# untitled.net
KiCad netlist of a schematic drawn in EAGLE
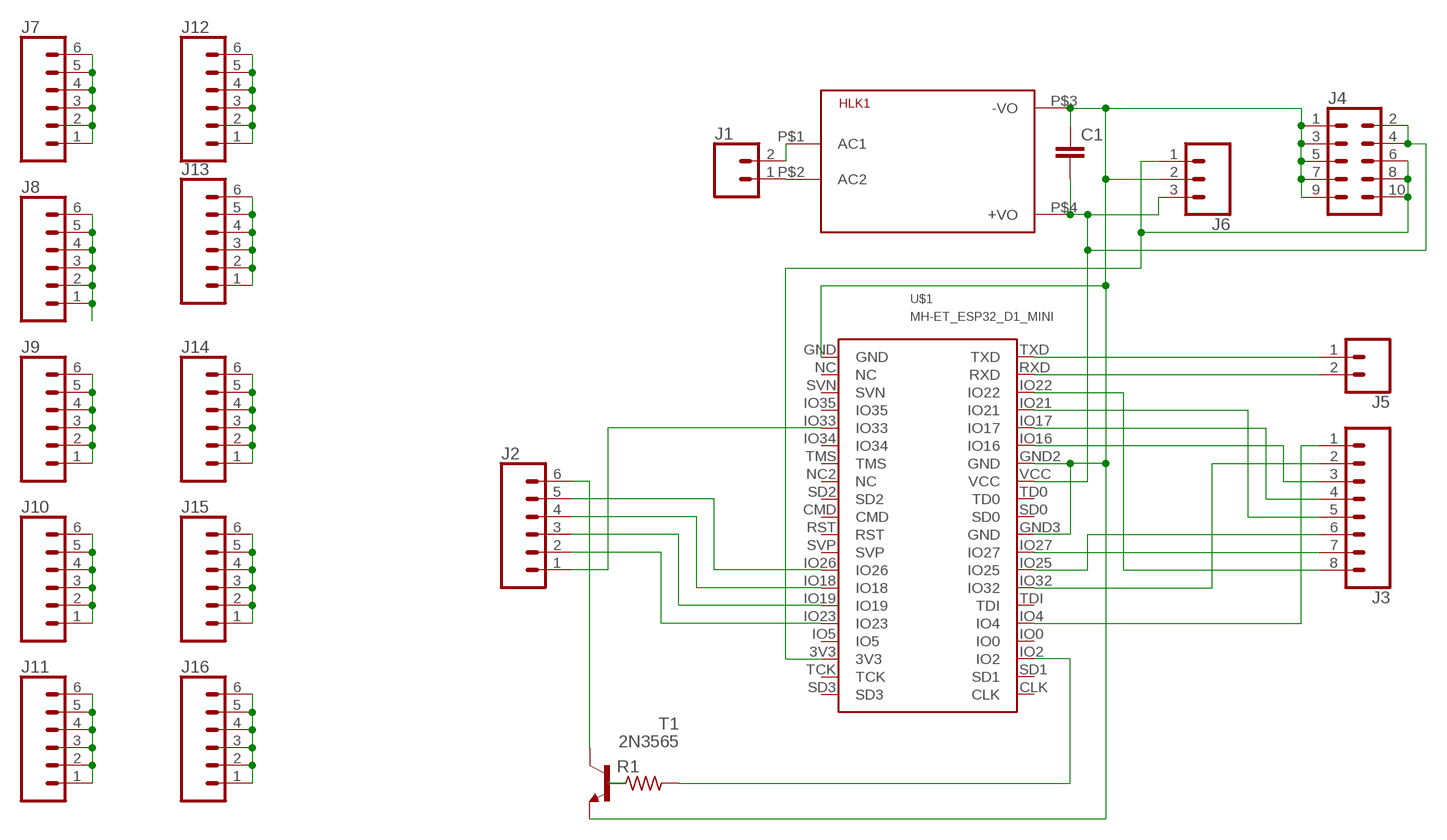
[diagram p0: schematic, sheet 1]

(export (version "E")
  (design (tool "Eeschema 10.0.6"))
  (components
    (comp (ref "C1")
      (value "C2.5/2")
      (footprint "eagle-import:C2.5-2")
      (libsource (lib "eagle-import") (part "C2.5/2"))
    )
    (comp (ref "HLK1")
      (value "HLK-PM013W")
      (footprint "eagle-import:HLK-PM01")
      (libsource (lib "eagle-import") (part "HLK-PM013W"))
    )
    (comp (ref "J1")
      (value "CONN_023.5MM")
      (footprint "eagle-import:SCREWTERMINAL-3.5MM-2")
      (libsource (lib "eagle-import") (part "CONN_023.5MM"))
    )
    (comp (ref "J2")
      (value "CONN_063.5MM-6")
      (footprint "eagle-import:SCREWTERMINAL-3.5MM-6")
      (libsource (lib "eagle-import") (part "CONN_063.5MM-6"))
    )
    (comp (ref "J3")
      (value "CONN_083.5MM-8")
      (footprint "eagle-import:SCREWTERMINAL-3.5MM-8")
      (libsource (lib "eagle-import") (part "CONN_083.5MM-8"))
    )
    (comp (ref "J4")
      (value "CONN_05X2NO_SILK")
      (footprint "eagle-import:2X5_NOSILK")
      (libsource (lib "eagle-import") (part "CONN_05X2NO_SILK"))
    )
    (comp (ref "J5")
      (value "CONN_02")
      (footprint "eagle-import:1X02")
      (libsource (lib "eagle-import") (part "CONN_02"))
    )
    (comp (ref "J6")
      (value "CONN_03SCREW")
      (footprint "eagle-import:SCREWTERMINAL-3.5MM-3")
      (libsource (lib "eagle-import") (part "CONN_03SCREW"))
    )
    (comp (ref "J7")
      (value "CONN_06SILK_FEMALE_PTH")
      (footprint "eagle-import:1X06")
      (libsource (lib "eagle-import") (part "CONN_06SILK_FEMALE_PTH"))
    )
    (comp (ref "J8")
      (value "CONN_06SILK_FEMALE_PTH")
      (footprint "eagle-import:1X06")
      (libsource (lib "eagle-import") (part "CONN_06SILK_FEMALE_PTH"))
    )
    (comp (ref "J9")
      (value "CONN_06SILK_FEMALE_PTH")
      (footprint "eagle-import:1X06")
      (libsource (lib "eagle-import") (part "CONN_06SILK_FEMALE_PTH"))
    )
    (comp (ref "J10")
      (value "CONN_06SILK_FEMALE_PTH")
      (footprint "eagle-import:1X06")
      (libsource (lib "eagle-import") (part "CONN_06SILK_FEMALE_PTH"))
    )
    (comp (ref "J11")
      (value "CONN_06SILK_FEMALE_PTH")
      (footprint "eagle-import:1X06")
      (libsource (lib "eagle-import") (part "CONN_06SILK_FEMALE_PTH"))
    )
    (comp (ref "J12")
      (value "CONN_06SILK_FEMALE_PTH")
      (footprint "eagle-import:1X06")
      (libsource (lib "eagle-import") (part "CONN_06SILK_FEMALE_PTH"))
    )
    (comp (ref "J13")
      (value "CONN_06SILK_FEMALE_PTH")
      (footprint "eagle-import:1X06")
      (libsource (lib "eagle-import") (part "CONN_06SILK_FEMALE_PTH"))
    )
    (comp (ref "J14")
      (value "CONN_06SILK_FEMALE_PTH")
      (footprint "eagle-import:1X06")
      (libsource (lib "eagle-import") (part "CONN_06SILK_FEMALE_PTH"))
    )
    (comp (ref "J15")
      (value "CONN_06SILK_FEMALE_PTH")
      (footprint "eagle-import:1X06")
      (libsource (lib "eagle-import") (part "CONN_06SILK_FEMALE_PTH"))
    )
    (comp (ref "J16")
      (value "CONN_06SILK_FEMALE_PTH")
      (footprint "eagle-import:1X06")
      (libsource (lib "eagle-import") (part "CONN_06SILK_FEMALE_PTH"))
    )
    (comp (ref "R1")
      (value "R-US_0204/5")
      (footprint "eagle-import:0204_5")
      (libsource (lib "eagle-import") (part "R-US_0204/5"))
    )
    (comp (ref "T1")
      (value "2N3565")
      (footprint "eagle-import:TO92")
      (libsource (lib "eagle-import") (part "2N3565"))
    )
    (comp (ref "U$1")
      (value "MH-ET_ESP32_D1_MINI")
      (footprint "eagle-import:MH-ET_ESP32_D1_MINI")
      (libsource (lib "eagle-import") (part "MH-ET_ESP32_D1_MINI"))
    )
  )
  (nets
    (net (code "1") (name "Net-(HLK1-+VO)") (class "Default")
      (node (ref "C1") (pin "2") (pinfunction "2_2") (pintype "passive"))
      (node (ref "HLK1") (pin "P$4") (pinfunction "+VO_P$4") (pintype "bidirectional"))
      (node (ref "J4") (pin "2") (pinfunction "2_2") (pintype "passive"))
      (node (ref "J4") (pin "4") (pinfunction "4_4") (pintype "passive"))
      (node (ref "J6") (pin "3") (pinfunction "3_3") (pintype "passive"))
      (node (ref "U$1") (pin "VCC") (pinfunction "VCC_VCC") (pintype "bidirectional"))
    )
    (net (code "2") (name "Net-(HLK1--VO)") (class "Default")
      (node (ref "C1") (pin "1") (pinfunction "1_1") (pintype "passive"))
      (node (ref "HLK1") (pin "P$3") (pinfunction "-VO_P$3") (pintype "bidirectional"))
      (node (ref "J4") (pin "1") (pinfunction "1_1") (pintype "passive"))
      (node (ref "J4") (pin "3") (pinfunction "3_3") (pintype "passive"))
      (node (ref "J4") (pin "5") (pinfunction "5_5") (pintype "passive"))
      (node (ref "J4") (pin "7") (pinfunction "7_7") (pintype "passive"))
      (node (ref "J4") (pin "9") (pinfunction "9_9") (pintype "passive"))
      (node (ref "J6") (pin "2") (pinfunction "2_2") (pintype "passive"))
      (node (ref "T1") (pin "3") (pinfunction "E_3") (pintype "passive"))
      (node (ref "U$1") (pin "GND") (pinfunction "GND_GND") (pintype "bidirectional"))
      (node (ref "U$1") (pin "GND2") (pinfunction "GND_GND2") (pintype "bidirectional"))
      (node (ref "U$1") (pin "GND3") (pinfunction "GND_GND3") (pintype "bidirectional"))
    )
    (net (code "3") (name "Net-(HLK1-AC1)") (class "Default")
      (node (ref "HLK1") (pin "P$1") (pinfunction "AC1_P$1") (pintype "bidirectional"))
      (node (ref "J1") (pin "2") (pinfunction "2_2") (pintype "passive"))
    )
    (net (code "4") (name "Net-(HLK1-AC2)") (class "Default")
      (node (ref "HLK1") (pin "P$2") (pinfunction "AC2_P$2") (pintype "bidirectional"))
      (node (ref "J1") (pin "1") (pinfunction "1_1") (pintype "passive"))
    )
    (net (code "5") (name "Net-(J2-Pad1)") (class "Default")
      (node (ref "J2") (pin "1") (pinfunction "1_1") (pintype "passive"))
      (node (ref "U$1") (pin "IO33") (pinfunction "IO33_IO33") (pintype "bidirectional"))
    )
    (net (code "6") (name "Net-(J2-Pad2)") (class "Default")
      (node (ref "J2") (pin "2") (pinfunction "2_2") (pintype "passive"))
      (node (ref "U$1") (pin "IO23") (pinfunction "IO23_IO23") (pintype "bidirectional"))
    )
    (net (code "7") (name "Net-(J2-Pad3)") (class "Default")
      (node (ref "J2") (pin "3") (pinfunction "3_3") (pintype "passive"))
      (node (ref "U$1") (pin "IO19") (pinfunction "IO19_IO19") (pintype "bidirectional"))
    )
    (net (code "8") (name "Net-(J2-Pad4)") (class "Default")
      (node (ref "J2") (pin "4") (pinfunction "4_4") (pintype "passive"))
      (node (ref "U$1") (pin "IO18") (pinfunction "IO18_IO18") (pintype "bidirectional"))
    )
    (net (code "9") (name "Net-(J2-Pad5)") (class "Default")
      (node (ref "J2") (pin "5") (pinfunction "5_5") (pintype "passive"))
      (node (ref "U$1") (pin "IO26") (pinfunction "IO26_IO26") (pintype "bidirectional"))
    )
    (net (code "10") (name "Net-(J3-Pad1)") (class "Default")
      (node (ref "J3") (pin "1") (pinfunction "1_1") (pintype "passive"))
      (node (ref "U$1") (pin "IO4") (pinfunction "IO4_IO4") (pintype "bidirectional"))
    )
    (net (code "11") (name "Net-(J3-Pad2)") (class "Default")
      (node (ref "J3") (pin "2") (pinfunction "2_2") (pintype "passive"))
      (node (ref "U$1") (pin "IO32") (pinfunction "IO32_IO32") (pintype "bidirectional"))
    )
    (net (code "12") (name "Net-(J3-Pad3)") (class "Default")
      (node (ref "J3") (pin "3") (pinfunction "3_3") (pintype "passive"))
      (node (ref "U$1") (pin "IO16") (pinfunction "IO16_IO16") (pintype "bidirectional"))
    )
    (net (code "13") (name "Net-(J3-Pad4)") (class "Default")
      (node (ref "J3") (pin "4") (pinfunction "4_4") (pintype "passive"))
      (node (ref "U$1") (pin "IO17") (pinfunction "IO17_IO17") (pintype "bidirectional"))
    )
    (net (code "14") (name "Net-(J3-Pad5)") (class "Default")
      (node (ref "J3") (pin "5") (pinfunction "5_5") (pintype "passive"))
      (node (ref "U$1") (pin "IO21") (pinfunction "IO21_IO21") (pintype "bidirectional"))
    )
    (net (code "15") (name "Net-(J3-Pad6)") (class "Default")
      (node (ref "J3") (pin "6") (pinfunction "6_6") (pintype "passive"))
      (node (ref "U$1") (pin "IO25") (pinfunction "IO25_IO25") (pintype "bidirectional"))
    )
    (net (code "16") (name "Net-(J3-Pad7)") (class "Default")
      (node (ref "J3") (pin "7") (pinfunction "7_7") (pintype "passive"))
      (node (ref "U$1") (pin "IO27") (pinfunction "IO27_IO27") (pintype "bidirectional"))
    )
    (net (code "17") (name "Net-(J3-Pad8)") (class "Default")
      (node (ref "J3") (pin "8") (pinfunction "8_8") (pintype "passive"))
      (node (ref "U$1") (pin "IO22") (pinfunction "IO22_IO22") (pintype "bidirectional"))
    )
    (net (code "18") (name "Net-(J4-Pad10)") (class "Default")
      (node (ref "J4") (pin "10") (pinfunction "10_10") (pintype "passive"))
      (node (ref "J4") (pin "6") (pinfunction "6_6") (pintype "passive"))
      (node (ref "J4") (pin "8") (pinfunction "8_8") (pintype "passive"))
      (node (ref "J6") (pin "1") (pinfunction "1_1") (pintype "passive"))
      (node (ref "U$1") (pin "3V3") (pinfunction "3V3_3V3") (pintype "bidirectional"))
    )
    (net (code "19") (name "Net-(J5-Pad1)") (class "Default")
      (node (ref "J5") (pin "1") (pinfunction "1_1") (pintype "passive"))
      (node (ref "U$1") (pin "TXD") (pinfunction "TXD_TXD") (pintype "bidirectional"))
    )
    (net (code "20") (name "Net-(J5-Pad2)") (class "Default")
      (node (ref "J5") (pin "2") (pinfunction "2_2") (pintype "passive"))
      (node (ref "U$1") (pin "RXD") (pinfunction "RXD_RXD") (pintype "bidirectional"))
    )
    (net (code "21") (name "Net-(J7-Pad1)") (class "Default")
      (node (ref "J7") (pin "1") (pinfunction "1_1") (pintype "passive"))
      (node (ref "J7") (pin "2") (pinfunction "2_2") (pintype "passive"))
      (node (ref "J7") (pin "3") (pinfunction "3_3") (pintype "passive"))
      (node (ref "J7") (pin "4") (pinfunction "4_4") (pintype "passive"))
      (node (ref "J7") (pin "5") (pinfunction "5_5") (pintype "passive"))
      (node (ref "J7") (pin "6") (pinfunction "6_6") (pintype "passive"))
    )
    (net (code "22") (name "Net-(J8-Pad1)") (class "Default")
      (node (ref "J8") (pin "1") (pinfunction "1_1") (pintype "passive"))
      (node (ref "J8") (pin "2") (pinfunction "2_2") (pintype "passive"))
      (node (ref "J8") (pin "3") (pinfunction "3_3") (pintype "passive"))
      (node (ref "J8") (pin "4") (pinfunction "4_4") (pintype "passive"))
      (node (ref "J8") (pin "5") (pinfunction "5_5") (pintype "passive"))
      (node (ref "J8") (pin "6") (pinfunction "6_6") (pintype "passive"))
    )
    (net (code "23") (name "Net-(J9-Pad1)") (class "Default")
      (node (ref "J9") (pin "1") (pinfunction "1_1") (pintype "passive"))
      (node (ref "J9") (pin "2") (pinfunction "2_2") (pintype "passive"))
      (node (ref "J9") (pin "3") (pinfunction "3_3") (pintype "passive"))
      (node (ref "J9") (pin "4") (pinfunction "4_4") (pintype "passive"))
      (node (ref "J9") (pin "5") (pinfunction "5_5") (pintype "passive"))
      (node (ref "J9") (pin "6") (pinfunction "6_6") (pintype "passive"))
    )
    (net (code "24") (name "Net-(J10-Pad1)") (class "Default")
      (node (ref "J10") (pin "1") (pinfunction "1_1") (pintype "passive"))
      (node (ref "J10") (pin "2") (pinfunction "2_2") (pintype "passive"))
      (node (ref "J10") (pin "3") (pinfunction "3_3") (pintype "passive"))
      (node (ref "J10") (pin "4") (pinfunction "4_4") (pintype "passive"))
      (node (ref "J10") (pin "5") (pinfunction "5_5") (pintype "passive"))
      (node (ref "J10") (pin "6") (pinfunction "6_6") (pintype "passive"))
    )
    (net (code "25") (name "Net-(J11-Pad1)") (class "Default")
      (node (ref "J11") (pin "1") (pinfunction "1_1") (pintype "passive"))
      (node (ref "J11") (pin "2") (pinfunction "2_2") (pintype "passive"))
      (node (ref "J11") (pin "3") (pinfunction "3_3") (pintype "passive"))
      (node (ref "J11") (pin "4") (pinfunction "4_4") (pintype "passive"))
      (node (ref "J11") (pin "5") (pinfunction "5_5") (pintype "passive"))
      (node (ref "J11") (pin "6") (pinfunction "6_6") (pintype "passive"))
    )
    (net (code "26") (name "Net-(J12-Pad1)") (class "Default")
      (node (ref "J12") (pin "1") (pinfunction "1_1") (pintype "passive"))
      (node (ref "J12") (pin "2") (pinfunction "2_2") (pintype "passive"))
      (node (ref "J12") (pin "3") (pinfunction "3_3") (pintype "passive"))
      (node (ref "J12") (pin "4") (pinfunction "4_4") (pintype "passive"))
      (node (ref "J12") (pin "5") (pinfunction "5_5") (pintype "passive"))
      (node (ref "J12") (pin "6") (pinfunction "6_6") (pintype "passive"))
    )
    (net (code "27") (name "Net-(J13-Pad1)") (class "Default")
      (node (ref "J13") (pin "1") (pinfunction "1_1") (pintype "passive"))
      (node (ref "J13") (pin "2") (pinfunction "2_2") (pintype "passive"))
      (node (ref "J13") (pin "3") (pinfunction "3_3") (pintype "passive"))
      (node (ref "J13") (pin "4") (pinfunction "4_4") (pintype "passive"))
      (node (ref "J13") (pin "5") (pinfunction "5_5") (pintype "passive"))
      (node (ref "J13") (pin "6") (pinfunction "6_6") (pintype "passive"))
    )
    (net (code "28") (name "Net-(J14-Pad1)") (class "Default")
      (node (ref "J14") (pin "1") (pinfunction "1_1") (pintype "passive"))
      (node (ref "J14") (pin "2") (pinfunction "2_2") (pintype "passive"))
      (node (ref "J14") (pin "3") (pinfunction "3_3") (pintype "passive"))
      (node (ref "J14") (pin "4") (pinfunction "4_4") (pintype "passive"))
      (node (ref "J14") (pin "5") (pinfunction "5_5") (pintype "passive"))
      (node (ref "J14") (pin "6") (pinfunction "6_6") (pintype "passive"))
    )
    (net (code "29") (name "Net-(J15-Pad1)") (class "Default")
      (node (ref "J15") (pin "1") (pinfunction "1_1") (pintype "passive"))
      (node (ref "J15") (pin "2") (pinfunction "2_2") (pintype "passive"))
      (node (ref "J15") (pin "3") (pinfunction "3_3") (pintype "passive"))
      (node (ref "J15") (pin "4") (pinfunction "4_4") (pintype "passive"))
      (node (ref "J15") (pin "5") (pinfunction "5_5") (pintype "passive"))
      (node (ref "J15") (pin "6") (pinfunction "6_6") (pintype "passive"))
    )
    (net (code "30") (name "Net-(J16-Pad1)") (class "Default")
      (node (ref "J16") (pin "1") (pinfunction "1_1") (pintype "passive"))
      (node (ref "J16") (pin "2") (pinfunction "2_2") (pintype "passive"))
      (node (ref "J16") (pin "3") (pinfunction "3_3") (pintype "passive"))
      (node (ref "J16") (pin "4") (pinfunction "4_4") (pintype "passive"))
      (node (ref "J16") (pin "5") (pinfunction "5_5") (pintype "passive"))
      (node (ref "J16") (pin "6") (pinfunction "6_6") (pintype "passive"))
    )
    (net (code "31") (name "Net-(R1-Pad2)") (class "Default")
      (node (ref "R1") (pin "2") (pinfunction "2_2") (pintype "passive"))
      (node (ref "U$1") (pin "IO2") (pinfunction "IO2_IO2") (pintype "bidirectional"))
    )
    (net (code "32") (name "Net-(T1-B)") (class "Default")
      (node (ref "R1") (pin "1") (pinfunction "1_1") (pintype "passive"))
      (node (ref "T1") (pin "2") (pinfunction "B_2") (pintype "passive"))
    )
    (net (code "33") (name "Net-(T1-C)") (class "Default")
      (node (ref "J2") (pin "6") (pinfunction "6_6") (pintype "passive"))
      (node (ref "T1") (pin "1") (pinfunction "C_1") (pintype "passive"))
    )
    (net (code "34") (name "unconnected-(U$1-NC-PadNC2)") (class "Default")
      (node (ref "U$1") (pin "NC2") (pinfunction "NC_NC2") (pintype "bidirectional"))
    )
    (net (code "35") (name "unconnected-(U$1-PadCLK)") (class "Default")
      (node (ref "U$1") (pin "CLK") (pinfunction "CLK_CLK") (pintype "bidirectional"))
    )
    (net (code "36") (name "unconnected-(U$1-PadCMD)") (class "Default")
      (node (ref "U$1") (pin "CMD") (pinfunction "CMD_CMD") (pintype "bidirectional"))
    )
    (net (code "37") (name "unconnected-(U$1-PadIO0)") (class "Default")
      (node (ref "U$1") (pin "IO0") (pinfunction "IO0_IO0") (pintype "bidirectional"))
    )
    (net (code "38") (name "unconnected-(U$1-PadIO5)") (class "Default")
      (node (ref "U$1") (pin "IO5") (pinfunction "IO5_IO5") (pintype "bidirectional"))
    )
    (net (code "39") (name "unconnected-(U$1-PadIO34)") (class "Default")
      (node (ref "U$1") (pin "IO34") (pinfunction "IO34_IO34") (pintype "bidirectional"))
    )
    (net (code "40") (name "unconnected-(U$1-PadIO35)") (class "Default")
      (node (ref "U$1") (pin "IO35") (pinfunction "IO35_IO35") (pintype "bidirectional"))
    )
    (net (code "41") (name "unconnected-(U$1-PadNC)") (class "Default")
      (node (ref "U$1") (pin "NC") (pinfunction "NC_NC") (pintype "bidirectional"))
    )
    (net (code "42") (name "unconnected-(U$1-PadRST)") (class "Default")
      (node (ref "U$1") (pin "RST") (pinfunction "RST_RST") (pintype "bidirectional"))
    )
    (net (code "43") (name "unconnected-(U$1-PadSD0)") (class "Default")
      (node (ref "U$1") (pin "SD0") (pinfunction "SD0_SD0") (pintype "bidirectional"))
    )
    (net (code "44") (name "unconnected-(U$1-PadSD1)") (class "Default")
      (node (ref "U$1") (pin "SD1") (pinfunction "SD1_SD1") (pintype "bidirectional"))
    )
    (net (code "45") (name "unconnected-(U$1-PadSD2)") (class "Default")
      (node (ref "U$1") (pin "SD2") (pinfunction "SD2_SD2") (pintype "bidirectional"))
    )
    (net (code "46") (name "unconnected-(U$1-PadSD3)") (class "Default")
      (node (ref "U$1") (pin "SD3") (pinfunction "SD3_SD3") (pintype "bidirectional"))
    )
    (net (code "47") (name "unconnected-(U$1-PadSVN)") (class "Default")
      (node (ref "U$1") (pin "SVN") (pinfunction "SVN_SVN") (pintype "bidirectional"))
    )
    (net (code "48") (name "unconnected-(U$1-PadSVP)") (class "Default")
      (node (ref "U$1") (pin "SVP") (pinfunction "SVP_SVP") (pintype "bidirectional"))
    )
    (net (code "49") (name "unconnected-(U$1-PadTCK)") (class "Default")
      (node (ref "U$1") (pin "TCK") (pinfunction "TCK_TCK") (pintype "bidirectional"))
    )
    (net (code "50") (name "unconnected-(U$1-PadTD0)") (class "Default")
      (node (ref "U$1") (pin "TD0") (pinfunction "TD0_TD0") (pintype "bidirectional"))
    )
    (net (code "51") (name "unconnected-(U$1-PadTDI)") (class "Default")
      (node (ref "U$1") (pin "TDI") (pinfunction "TDI_TDI") (pintype "bidirectional"))
    )
    (net (code "52") (name "unconnected-(U$1-PadTMS)") (class "Default")
      (node (ref "U$1") (pin "TMS") (pinfunction "TMS_TMS") (pintype "bidirectional"))
    )
  )
)
